# blimpy-1_0-A.net
KiCad netlist of a schematic drawn in EAGLE
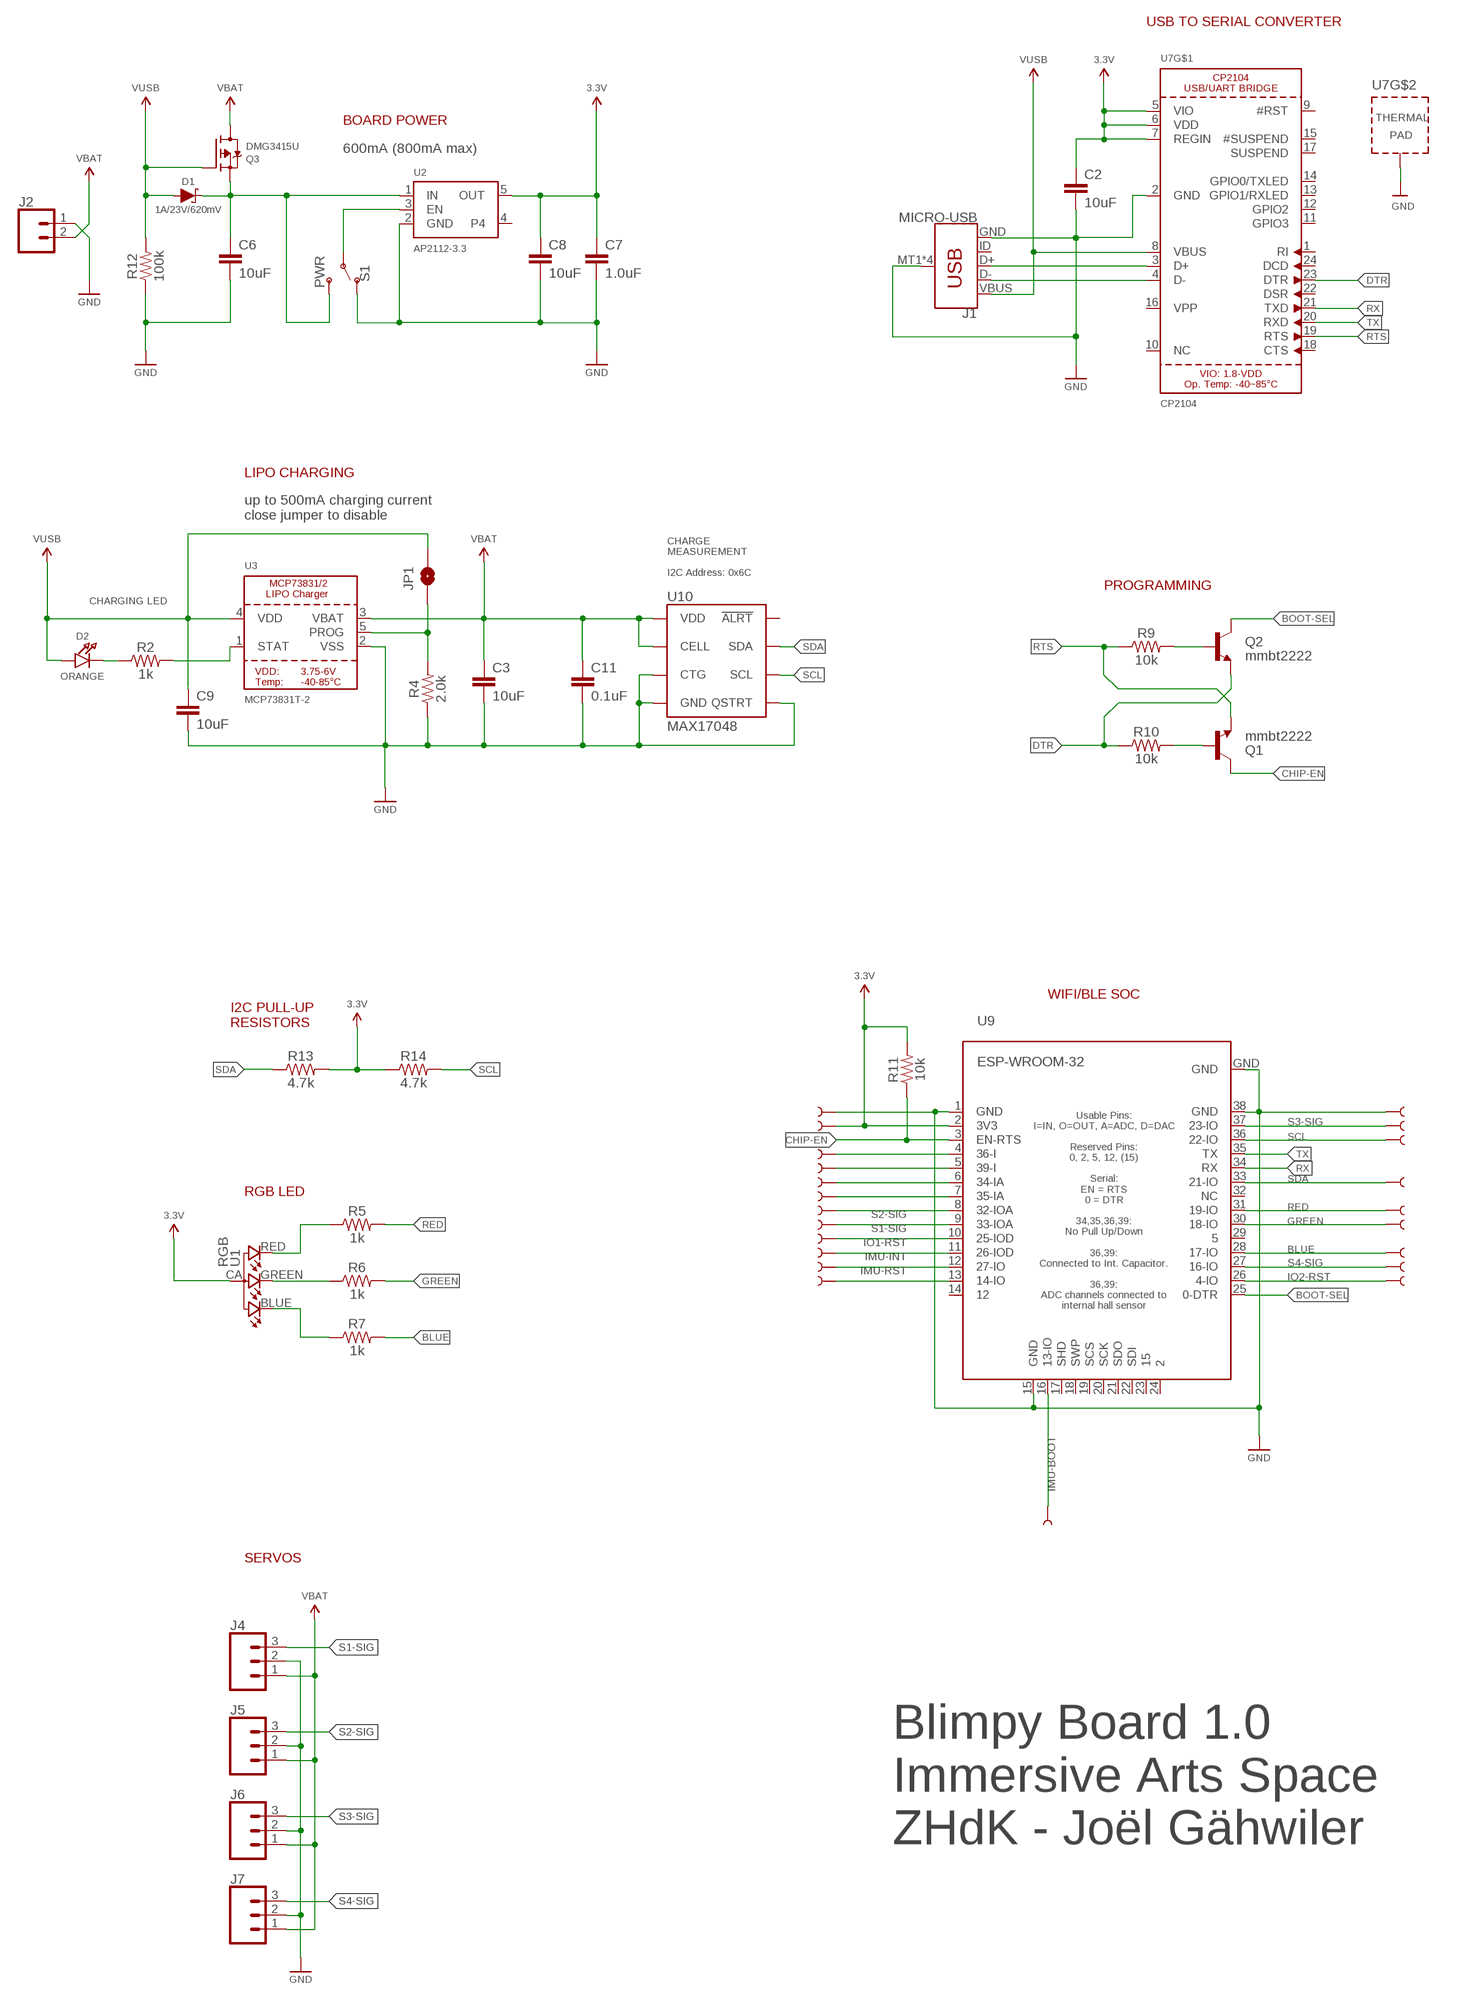
[diagram p0: schematic, sheet 1, part 1 of 2]
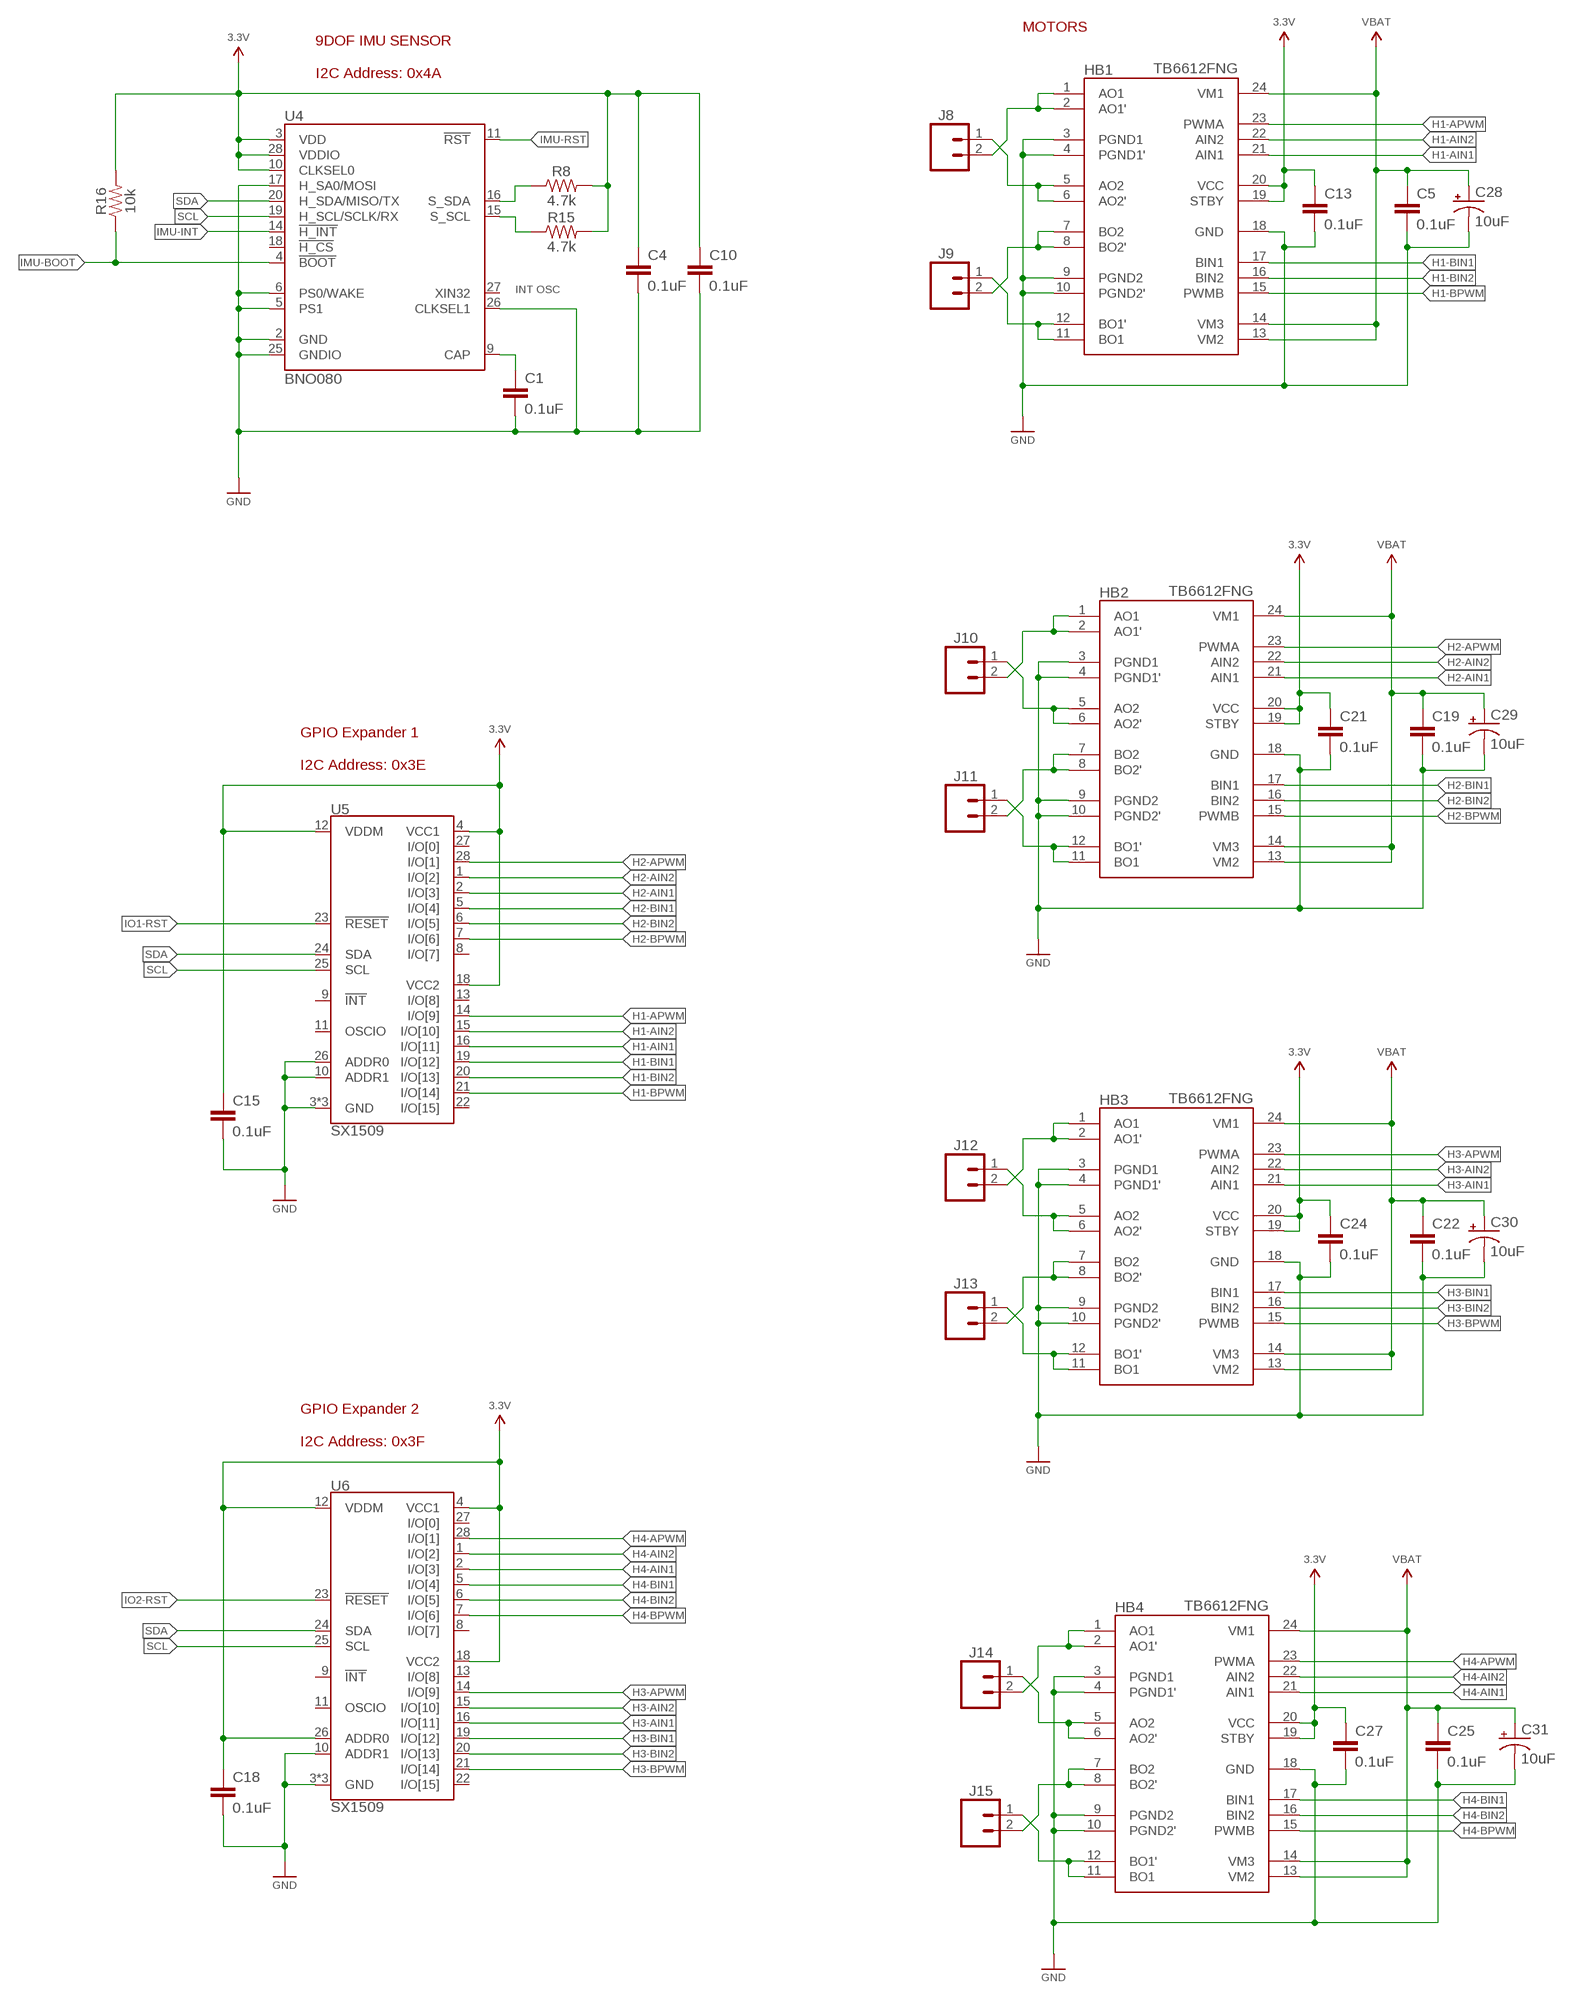
[diagram p1: schematic, sheet 1, part 2 of 2]

(export (version "E")
  (design (tool "Eeschema 10.0.6"))
  (components
    (comp (ref "C1")
      (value "0.1uF")
      (footprint "eagle-import:0603")
      (libsource (lib "eagle-import") (part "0.1UF-0603-25V-5%"))
    )
    (comp (ref "C2")
      (value "10uF")
      (footprint "eagle-import:0603")
      (libsource (lib "eagle-import") (part "10UF-0603-6.3V-20%"))
    )
    (comp (ref "C3")
      (value "10uF")
      (footprint "eagle-import:0603")
      (libsource (lib "eagle-import") (part "10UF-0603-6.3V-20%"))
    )
    (comp (ref "C4")
      (value "0.1uF")
      (footprint "eagle-import:0603")
      (libsource (lib "eagle-import") (part "0.1UF-0603-25V-5%"))
    )
    (comp (ref "C5")
      (value "0.1uF")
      (footprint "eagle-import:0603")
      (libsource (lib "eagle-import") (part "0.1UF-0603-25V-5%"))
    )
    (comp (ref "C6")
      (value "10uF")
      (footprint "eagle-import:0603")
      (libsource (lib "eagle-import") (part "10UF-0603-6.3V-20%"))
    )
    (comp (ref "C7")
      (value "1.0uF")
      (footprint "eagle-import:0603")
      (libsource (lib "eagle-import") (part "1.0UF-0603-16V-10%"))
    )
    (comp (ref "C8")
      (value "10uF")
      (footprint "eagle-import:0603")
      (libsource (lib "eagle-import") (part "10UF-0603-6.3V-20%"))
    )
    (comp (ref "C9")
      (value "10uF")
      (footprint "eagle-import:0603")
      (libsource (lib "eagle-import") (part "10UF-0603-6.3V-20%"))
    )
    (comp (ref "C10")
      (value "0.1uF")
      (footprint "eagle-import:0603")
      (libsource (lib "eagle-import") (part "0.1UF-0603-25V-5%"))
    )
    (comp (ref "C11")
      (value "0.1uF")
      (footprint "eagle-import:0603")
      (libsource (lib "eagle-import") (part "SparkFun-Capacitors_510_0.1UF-0603-25V-5%"))
    )
    (comp (ref "C13")
      (value "0.1uF")
      (footprint "eagle-import:0603")
      (libsource (lib "eagle-import") (part "0.1UF-0603-25V-5%"))
    )
    (comp (ref "C15")
      (value "0.1uF")
      (footprint "eagle-import:0603")
      (libsource (lib "eagle-import") (part "SparkFun-Capacitors_510_0.1UF-0603-25V-5%"))
    )
    (comp (ref "C18")
      (value "0.1uF")
      (footprint "eagle-import:0603")
      (libsource (lib "eagle-import") (part "SparkFun-Capacitors_510_0.1UF-0603-25V-5%"))
    )
    (comp (ref "C19")
      (value "0.1uF")
      (footprint "eagle-import:0603")
      (libsource (lib "eagle-import") (part "0.1UF-0603-25V-5%"))
    )
    (comp (ref "C21")
      (value "0.1uF")
      (footprint "eagle-import:0603")
      (libsource (lib "eagle-import") (part "0.1UF-0603-25V-5%"))
    )
    (comp (ref "C22")
      (value "0.1uF")
      (footprint "eagle-import:0603")
      (libsource (lib "eagle-import") (part "0.1UF-0603-25V-5%"))
    )
    (comp (ref "C24")
      (value "0.1uF")
      (footprint "eagle-import:0603")
      (libsource (lib "eagle-import") (part "0.1UF-0603-25V-5%"))
    )
    (comp (ref "C25")
      (value "0.1uF")
      (footprint "eagle-import:0603")
      (libsource (lib "eagle-import") (part "0.1UF-0603-25V-5%"))
    )
    (comp (ref "C27")
      (value "0.1uF")
      (footprint "eagle-import:0603")
      (libsource (lib "eagle-import") (part "0.1UF-0603-25V-5%"))
    )
    (comp (ref "C28")
      (value "10uF")
      (footprint "eagle-import:EIA3216")
      (libsource (lib "eagle-import") (part "10UF-POLAR-EIA3216-16V-10%(TANT)"))
    )
    (comp (ref "C29")
      (value "10uF")
      (footprint "eagle-import:EIA3216")
      (libsource (lib "eagle-import") (part "10UF-POLAR-EIA3216-16V-10%(TANT)"))
    )
    (comp (ref "C30")
      (value "10uF")
      (footprint "eagle-import:EIA3216")
      (libsource (lib "eagle-import") (part "10UF-POLAR-EIA3216-16V-10%(TANT)"))
    )
    (comp (ref "C31")
      (value "10uF")
      (footprint "eagle-import:EIA3216")
      (libsource (lib "eagle-import") (part "10UF-POLAR-EIA3216-16V-10%(TANT)"))
    )
    (comp (ref "D1")
      (value "1A/23V/620mV")
      (footprint "eagle-import:SOD-323")
      (libsource (lib "eagle-import") (part "DIODE-SCHOTTKY-BAT20J"))
    )
    (comp (ref "D2")
      (value "ORANGE")
      (footprint "eagle-import:CHIPLED_0805_NOOUTLINE")
      (libsource (lib "eagle-import") (part "LED0805_NOOUTLINE"))
    )
    (comp (ref "HB1")
      (value "TB6612FNG")
      (footprint "eagle-import:SSOP24")
      (libsource (lib "eagle-import") (part "TB6612FNG"))
    )
    (comp (ref "HB2")
      (value "TB6612FNG")
      (footprint "eagle-import:SSOP24")
      (libsource (lib "eagle-import") (part "TB6612FNG"))
    )
    (comp (ref "HB3")
      (value "TB6612FNG")
      (footprint "eagle-import:SSOP24")
      (libsource (lib "eagle-import") (part "TB6612FNG"))
    )
    (comp (ref "HB4")
      (value "TB6612FNG")
      (footprint "eagle-import:SSOP24")
      (libsource (lib "eagle-import") (part "TB6612FNG"))
    )
    (comp (ref "J1")
      (value "MICRO-USB")
      (footprint "eagle-import:USB-MICROB")
      (libsource (lib "eagle-import") (part "USB_MICRO-B_SMT"))
    )
    (comp (ref "J2")
      (value "CONN_02-JST-2MM-SMT")
      (footprint "eagle-import:JST-2-SMD")
      (libsource (lib "eagle-import") (part "CONN_02-JST-2MM-SMT"))
    )
    (comp (ref "J4")
      (value "3-PIN SMD")
      (footprint "eagle-import:JST-3-SMD")
      (libsource (lib "eagle-import") (part "CONN_03JST-SMD"))
    )
    (comp (ref "J5")
      (value "3-PIN SMD")
      (footprint "eagle-import:JST-3-SMD")
      (libsource (lib "eagle-import") (part "CONN_03JST-SMD"))
    )
    (comp (ref "J6")
      (value "3-PIN SMD")
      (footprint "eagle-import:JST-3-SMD")
      (libsource (lib "eagle-import") (part "CONN_03JST-SMD"))
    )
    (comp (ref "J7")
      (value "3-PIN SMD")
      (footprint "eagle-import:JST-3-SMD")
      (libsource (lib "eagle-import") (part "CONN_03JST-SMD"))
    )
    (comp (ref "J8")
      (value "CONN_02-JST-2MM-SMT")
      (footprint "eagle-import:JST-2-SMD")
      (libsource (lib "eagle-import") (part "CONN_02-JST-2MM-SMT"))
    )
    (comp (ref "J9")
      (value "CONN_02-JST-2MM-SMT")
      (footprint "eagle-import:JST-2-SMD")
      (libsource (lib "eagle-import") (part "CONN_02-JST-2MM-SMT"))
    )
    (comp (ref "J10")
      (value "CONN_02-JST-2MM-SMT")
      (footprint "eagle-import:JST-2-SMD")
      (libsource (lib "eagle-import") (part "CONN_02-JST-2MM-SMT"))
    )
    (comp (ref "J11")
      (value "CONN_02-JST-2MM-SMT")
      (footprint "eagle-import:JST-2-SMD")
      (libsource (lib "eagle-import") (part "CONN_02-JST-2MM-SMT"))
    )
    (comp (ref "J12")
      (value "CONN_02-JST-2MM-SMT")
      (footprint "eagle-import:JST-2-SMD")
      (libsource (lib "eagle-import") (part "CONN_02-JST-2MM-SMT"))
    )
    (comp (ref "J13")
      (value "CONN_02-JST-2MM-SMT")
      (footprint "eagle-import:JST-2-SMD")
      (libsource (lib "eagle-import") (part "CONN_02-JST-2MM-SMT"))
    )
    (comp (ref "J14")
      (value "CONN_02-JST-2MM-SMT")
      (footprint "eagle-import:JST-2-SMD")
      (libsource (lib "eagle-import") (part "CONN_02-JST-2MM-SMT"))
    )
    (comp (ref "J15")
      (value "CONN_02-JST-2MM-SMT")
      (footprint "eagle-import:JST-2-SMD")
      (libsource (lib "eagle-import") (part "CONN_02-JST-2MM-SMT"))
    )
    (comp (ref "JP1")
      (value "JUMPER-SMT_2_NO_SILK")
      (footprint "eagle-import:SMT-JUMPER_2_NO_SILK")
      (libsource (lib "eagle-import") (part "JUMPER-SMT_2_NO_SILK"))
    )
    (comp (ref "Q1")
      (value "mmbt2222")
      (footprint "eagle-import:SOT23-3")
      (libsource (lib "eagle-import") (part "TRANSISTOR_NPNSOT23-3"))
    )
    (comp (ref "Q2")
      (value "mmbt2222")
      (footprint "eagle-import:SOT23-3")
      (libsource (lib "eagle-import") (part "TRANSISTOR_NPNSOT23-3"))
    )
    (comp (ref "Q3")
      (value "DMG3415U")
      (footprint "eagle-import:SOT23-R")
      (libsource (lib "eagle-import") (part "MOSFET-P"))
    )
    (comp (ref "R2")
      (value "1k")
      (footprint "eagle-import:0603")
      (libsource (lib "eagle-import") (part "1KOHM-0603-1/10W-1%"))
    )
    (comp (ref "R4")
      (value "2.0k")
      (footprint "eagle-import:0603")
      (libsource (lib "eagle-import") (part "2.0KOHM-0603-1/10W-5%"))
    )
    (comp (ref "R5")
      (value "1k")
      (footprint "eagle-import:0603")
      (libsource (lib "eagle-import") (part "1KOHM-0603-1/10W-1%"))
    )
    (comp (ref "R6")
      (value "1k")
      (footprint "eagle-import:0603")
      (libsource (lib "eagle-import") (part "1KOHM-0603-1/10W-1%"))
    )
    (comp (ref "R7")
      (value "1k")
      (footprint "eagle-import:0603")
      (libsource (lib "eagle-import") (part "1KOHM-0603-1/10W-1%"))
    )
    (comp (ref "R8")
      (value "4.7k")
      (footprint "eagle-import:0603")
      (libsource (lib "eagle-import") (part "4.7KOHM-0603-1/10W-1%"))
    )
    (comp (ref "R9")
      (value "10k")
      (footprint "eagle-import:0603")
      (libsource (lib "eagle-import") (part "10KOHM-0603-1/10W-1%"))
    )
    (comp (ref "R10")
      (value "10k")
      (footprint "eagle-import:0603")
      (libsource (lib "eagle-import") (part "10KOHM-0603-1/10W-1%"))
    )
    (comp (ref "R11")
      (value "10k")
      (footprint "eagle-import:0603")
      (libsource (lib "eagle-import") (part "10KOHM-0603-1/10W-1%"))
    )
    (comp (ref "R12")
      (value "100k")
      (footprint "eagle-import:0603")
      (libsource (lib "eagle-import") (part "100KOHM-0603-1/10W-1%"))
    )
    (comp (ref "R13")
      (value "4.7k")
      (footprint "eagle-import:0603")
      (libsource (lib "eagle-import") (part "4.7KOHM-0603-1/10W-1%"))
    )
    (comp (ref "R14")
      (value "4.7k")
      (footprint "eagle-import:0603")
      (libsource (lib "eagle-import") (part "4.7KOHM-0603-1/10W-1%"))
    )
    (comp (ref "R15")
      (value "4.7k")
      (footprint "eagle-import:0603")
      (libsource (lib "eagle-import") (part "4.7KOHM-0603-1/10W-1%"))
    )
    (comp (ref "R16")
      (value "10k")
      (footprint "eagle-import:0603")
      (libsource (lib "eagle-import") (part "10KOHM-0603-1/10W-1%"))
    )
    (comp (ref "S1")
      (value "PWR")
      (footprint "eagle-import:SWITCH_SPST_SMD_A")
      (libsource (lib "eagle-import") (part "SWITCH-SPDT-SMD-RIGHT-ANGLE"))
    )
    (comp (ref "TP1")
      (value "TEST-POINT3")
      (footprint "eagle-import:PAD.03X.03")
      (libsource (lib "eagle-import") (part "TEST-POINT3"))
    )
    (comp (ref "TP2")
      (value "TEST-POINT3")
      (footprint "eagle-import:PAD.03X.03")
      (libsource (lib "eagle-import") (part "TEST-POINT3"))
    )
    (comp (ref "TP3")
      (value "TEST-POINT3")
      (footprint "eagle-import:PAD.03X.03")
      (libsource (lib "eagle-import") (part "TEST-POINT3"))
    )
    (comp (ref "TP4")
      (value "TEST-POINT3")
      (footprint "eagle-import:PAD.03X.03")
      (libsource (lib "eagle-import") (part "TEST-POINT3"))
    )
    (comp (ref "TP5")
      (value "TEST-POINT3")
      (footprint "eagle-import:PAD.03X.03")
      (libsource (lib "eagle-import") (part "TEST-POINT3"))
    )
    (comp (ref "TP6")
      (value "TEST-POINT3")
      (footprint "eagle-import:PAD.03X.03")
      (libsource (lib "eagle-import") (part "TEST-POINT3"))
    )
    (comp (ref "TP7")
      (value "TEST-POINT3")
      (footprint "eagle-import:PAD.03X.03")
      (libsource (lib "eagle-import") (part "TEST-POINT3"))
    )
    (comp (ref "TP8")
      (value "TEST-POINT3")
      (footprint "eagle-import:PAD.03X.03")
      (libsource (lib "eagle-import") (part "TEST-POINT3"))
    )
    (comp (ref "TP9")
      (value "TEST-POINT3")
      (footprint "eagle-import:PAD.03X.03")
      (libsource (lib "eagle-import") (part "TEST-POINT3"))
    )
    (comp (ref "TP10")
      (value "TEST-POINT3")
      (footprint "eagle-import:PAD.03X.03")
      (libsource (lib "eagle-import") (part "TEST-POINT3"))
    )
    (comp (ref "TP11")
      (value "TEST-POINT3")
      (footprint "eagle-import:PAD.03X.03")
      (libsource (lib "eagle-import") (part "TEST-POINT3"))
    )
    (comp (ref "TP12")
      (value "TEST-POINT3")
      (footprint "eagle-import:PAD.03X.03")
      (libsource (lib "eagle-import") (part "TEST-POINT3"))
    )
    (comp (ref "TP13")
      (value "TEST-POINT3")
      (footprint "eagle-import:PAD.03X.03")
      (libsource (lib "eagle-import") (part "TEST-POINT3"))
    )
    (comp (ref "TP14")
      (value "TEST-POINT3")
      (footprint "eagle-import:PAD.03X.03")
      (libsource (lib "eagle-import") (part "TEST-POINT3"))
    )
    (comp (ref "TP15")
      (value "TEST-POINT3")
      (footprint "eagle-import:PAD.03X.03")
      (libsource (lib "eagle-import") (part "TEST-POINT3"))
    )
    (comp (ref "TP16")
      (value "TEST-POINT3")
      (footprint "eagle-import:PAD.03X.03")
      (libsource (lib "eagle-import") (part "TEST-POINT3"))
    )
    (comp (ref "TP17")
      (value "TEST-POINT3")
      (footprint "eagle-import:PAD.03X.03")
      (libsource (lib "eagle-import") (part "TEST-POINT3"))
    )
    (comp (ref "TP18")
      (value "TEST-POINT3")
      (footprint "eagle-import:PAD.03X.03")
      (libsource (lib "eagle-import") (part "TEST-POINT3"))
    )
    (comp (ref "TP19")
      (value "TEST-POINT3")
      (footprint "eagle-import:PAD.03X.03")
      (libsource (lib "eagle-import") (part "TEST-POINT3"))
    )
    (comp (ref "TP20")
      (value "TEST-POINT3")
      (footprint "eagle-import:PAD.03X.03")
      (libsource (lib "eagle-import") (part "TEST-POINT3"))
    )
    (comp (ref "TP21")
      (value "TEST-POINT3")
      (footprint "eagle-import:PAD.03X.03")
      (libsource (lib "eagle-import") (part "TEST-POINT3"))
    )
    (comp (ref "TP22")
      (value "TEST-POINT3")
      (footprint "eagle-import:PAD.03X.03")
      (libsource (lib "eagle-import") (part "TEST-POINT3"))
    )
    (comp (ref "U1")
      (value "RGB")
      (footprint "eagle-import:PLCC4-2MM-RGB")
      (libsource (lib "eagle-import") (part "RGB-LED-CLMVB-FKARGB"))
    )
    (comp (ref "U2")
      (value "AP2112-3.3")
      (footprint "eagle-import:SOT23-5")
      (libsource (lib "eagle-import") (part "VREG_SOT23-5"))
    )
    (comp (ref "U3")
      (value "MCP73831T-2")
      (footprint "eagle-import:SOT23-5")
      (libsource (lib "eagle-import") (part "MCP73831/2"))
    )
    (comp (ref "U4")
      (value "BNO080")
      (footprint "eagle-import:LGA-28")
      (libsource (lib "eagle-import") (part "BNO080"))
    )
    (comp (ref "U5")
      (value "SX1509")
      (footprint "eagle-import:QFN-28")
      (libsource (lib "eagle-import") (part "SX1509"))
    )
    (comp (ref "U6")
      (value "SX1509")
      (footprint "eagle-import:QFN-28")
      (libsource (lib "eagle-import") (part "SX1509"))
    )
    (comp (ref "U7")
      (value "CP2104")
      (footprint "eagle-import:QFN24_4MM_SMSC")
      (libsource (lib "eagle-import") (part "CP2104"))
    )
    (comp (ref "U9")
      (value "ESP-WROOM-32")
      (footprint "eagle-import:ESP-WROOM-32")
      (libsource (lib "eagle-import") (part "ESP-WROOM-32"))
    )
    (comp (ref "U10")
      (value "MAX17048")
      (footprint "eagle-import:DFN-8")
      (libsource (lib "eagle-import") (part "MAX17048DFN8"))
    )
  )
  (nets
    (net (code "1") (name "3.3V") (class "Default")
      (node (ref "C10") (pin "1") (pinfunction "1_1") (pintype "passive"))
      (node (ref "C13") (pin "1") (pinfunction "1_1") (pintype "passive"))
      (node (ref "C15") (pin "1") (pinfunction "1_1") (pintype "passive"))
      (node (ref "C18") (pin "1") (pinfunction "1_1") (pintype "passive"))
      (node (ref "C2") (pin "1") (pinfunction "1_1") (pintype "passive"))
      (node (ref "C21") (pin "1") (pinfunction "1_1") (pintype "passive"))
      (node (ref "C24") (pin "1") (pinfunction "1_1") (pintype "passive"))
      (node (ref "C27") (pin "1") (pinfunction "1_1") (pintype "passive"))
      (node (ref "C4") (pin "1") (pinfunction "1_1") (pintype "passive"))
      (node (ref "C7") (pin "1") (pinfunction "1_1") (pintype "passive"))
      (node (ref "C8") (pin "1") (pinfunction "1_1") (pintype "passive"))
      (node (ref "HB1") (pin "19") (pinfunction "STBY_19") (pintype "input"))
      (node (ref "HB1") (pin "20") (pinfunction "VCC_20") (pintype "power_in"))
      (node (ref "HB2") (pin "19") (pinfunction "STBY_19") (pintype "input"))
      (node (ref "HB2") (pin "20") (pinfunction "VCC_20") (pintype "power_in"))
      (node (ref "HB3") (pin "19") (pinfunction "STBY_19") (pintype "input"))
      (node (ref "HB3") (pin "20") (pinfunction "VCC_20") (pintype "power_in"))
      (node (ref "HB4") (pin "19") (pinfunction "STBY_19") (pintype "input"))
      (node (ref "HB4") (pin "20") (pinfunction "VCC_20") (pintype "power_in"))
      (node (ref "R11") (pin "2") (pinfunction "2_2") (pintype "passive"))
      (node (ref "R13") (pin "2") (pinfunction "2_2") (pintype "passive"))
      (node (ref "R14") (pin "1") (pinfunction "1_1") (pintype "passive"))
      (node (ref "R15") (pin "2") (pinfunction "2_2") (pintype "passive"))
      (node (ref "R16") (pin "2") (pinfunction "2_2") (pintype "passive"))
      (node (ref "R8") (pin "2") (pinfunction "2_2") (pintype "passive"))
      (node (ref "TP11") (pin "P$1") (pinfunction "1_P$1") (pintype "bidirectional"))
      (node (ref "U1") (pin "CA") (pinfunction "1_CA") (pintype "passive"))
      (node (ref "U2") (pin "5") (pinfunction "OUT_5") (pintype "power_in"))
      (node (ref "U4") (pin "10") (pinfunction "CLKSEL0_10") (pintype "bidirectional"))
      (node (ref "U4") (pin "28") (pinfunction "VDDIO_28") (pintype "bidirectional"))
      (node (ref "U4") (pin "3") (pinfunction "VDD_3") (pintype "bidirectional"))
      (node (ref "U5") (pin "12") (pinfunction "VDDM_12") (pintype "bidirectional"))
      (node (ref "U5") (pin "18") (pinfunction "VCC2_18") (pintype "bidirectional"))
      (node (ref "U5") (pin "4") (pinfunction "VCC1_4") (pintype "bidirectional"))
      (node (ref "U6") (pin "12") (pinfunction "VDDM_12") (pintype "bidirectional"))
      (node (ref "U6") (pin "18") (pinfunction "VCC2_18") (pintype "bidirectional"))
      (node (ref "U6") (pin "26") (pinfunction "ADDR0_26") (pintype "bidirectional"))
      (node (ref "U6") (pin "4") (pinfunction "VCC1_4") (pintype "bidirectional"))
      (node (ref "U7") (pin "5") (pinfunction "VIO_5") (pintype "power_in"))
      (node (ref "U7") (pin "6") (pinfunction "VDD_6") (pintype "power_in"))
      (node (ref "U7") (pin "7") (pinfunction "REGIN_7") (pintype "power_in"))
      (node (ref "U9") (pin "2") (pinfunction "3V3_2") (pintype "bidirectional"))
    )
    (net (code "2") (name "BLUE") (class "Default")
      (node (ref "R7") (pin "2") (pinfunction "2_2") (pintype "passive"))
      (node (ref "TP22") (pin "P$1") (pinfunction "1_P$1") (pintype "bidirectional"))
      (node (ref "U9") (pin "28") (pinfunction "17-IO_28") (pintype "bidirectional"))
    )
    (net (code "3") (name "BOOT-SEL") (class "Default")
      (node (ref "Q2") (pin "3") (pinfunction "C_3") (pintype "passive"))
      (node (ref "U9") (pin "25") (pinfunction "0-DTR_25") (pintype "bidirectional"))
    )
    (net (code "4") (name "CHIP-EN") (class "Default")
      (node (ref "Q1") (pin "3") (pinfunction "C_3") (pintype "passive"))
      (node (ref "R11") (pin "1") (pinfunction "1_1") (pintype "passive"))
      (node (ref "U9") (pin "3") (pinfunction "EN-RTS_3") (pintype "bidirectional"))
    )
    (net (code "5") (name "DTR") (class "Default")
      (node (ref "Q2") (pin "2") (pinfunction "E_2") (pintype "passive"))
      (node (ref "R10") (pin "1") (pinfunction "1_1") (pintype "passive"))
      (node (ref "U7") (pin "23") (pinfunction "DTR_23") (pintype "output"))
    )
    (net (code "6") (name "GND") (class "Default")
      (node (ref "C1") (pin "2") (pinfunction "2_2") (pintype "passive"))
      (node (ref "C10") (pin "2") (pinfunction "2_2") (pintype "passive"))
      (node (ref "C11") (pin "2") (pinfunction "2_2") (pintype "passive"))
      (node (ref "C13") (pin "2") (pinfunction "2_2") (pintype "passive"))
      (node (ref "C15") (pin "2") (pinfunction "2_2") (pintype "passive"))
      (node (ref "C18") (pin "2") (pinfunction "2_2") (pintype "passive"))
      (node (ref "C19") (pin "2") (pinfunction "2_2") (pintype "passive"))
      (node (ref "C2") (pin "2") (pinfunction "2_2") (pintype "passive"))
      (node (ref "C21") (pin "2") (pinfunction "2_2") (pintype "passive"))
      (node (ref "C22") (pin "2") (pinfunction "2_2") (pintype "passive"))
      (node (ref "C24") (pin "2") (pinfunction "2_2") (pintype "passive"))
      (node (ref "C25") (pin "2") (pinfunction "2_2") (pintype "passive"))
      (node (ref "C27") (pin "2") (pinfunction "2_2") (pintype "passive"))
      (node (ref "C28") (pin "-") (pinfunction "-_-") (pintype "passive"))
      (node (ref "C29") (pin "-") (pinfunction "-_-") (pintype "passive"))
      (node (ref "C3") (pin "2") (pinfunction "2_2") (pintype "passive"))
      (node (ref "C30") (pin "-") (pinfunction "-_-") (pintype "passive"))
      (node (ref "C31") (pin "-") (pinfunction "-_-") (pintype "passive"))
      (node (ref "C4") (pin "2") (pinfunction "2_2") (pintype "passive"))
      (node (ref "C5") (pin "2") (pinfunction "2_2") (pintype "passive"))
      (node (ref "C6") (pin "2") (pinfunction "2_2") (pintype "passive"))
      (node (ref "C7") (pin "2") (pinfunction "2_2") (pintype "passive"))
      (node (ref "C8") (pin "2") (pinfunction "2_2") (pintype "passive"))
      (node (ref "C9") (pin "2") (pinfunction "2_2") (pintype "passive"))
      (node (ref "HB1") (pin "10") (pinfunction "PGND2'_10") (pintype "power_in"))
      (node (ref "HB1") (pin "18") (pinfunction "GND_18") (pintype "power_in"))
      (node (ref "HB1") (pin "3") (pinfunction "PGND1_3") (pintype "power_in"))
      (node (ref "HB1") (pin "4") (pinfunction "PGND1'_4") (pintype "power_in"))
      (node (ref "HB1") (pin "9") (pinfunction "PGND2_9") (pintype "power_in"))
      (node (ref "HB2") (pin "10") (pinfunction "PGND2'_10") (pintype "power_in"))
      (node (ref "HB2") (pin "18") (pinfunction "GND_18") (pintype "power_in"))
      (node (ref "HB2") (pin "3") (pinfunction "PGND1_3") (pintype "power_in"))
      (node (ref "HB2") (pin "4") (pinfunction "PGND1'_4") (pintype "power_in"))
      (node (ref "HB2") (pin "9") (pinfunction "PGND2_9") (pintype "power_in"))
      (node (ref "HB3") (pin "10") (pinfunction "PGND2'_10") (pintype "power_in"))
      (node (ref "HB3") (pin "18") (pinfunction "GND_18") (pintype "power_in"))
      (node (ref "HB3") (pin "3") (pinfunction "PGND1_3") (pintype "power_in"))
      (node (ref "HB3") (pin "4") (pinfunction "PGND1'_4") (pintype "power_in"))
      (node (ref "HB3") (pin "9") (pinfunction "PGND2_9") (pintype "power_in"))
      (node (ref "HB4") (pin "10") (pinfunction "PGND2'_10") (pintype "power_in"))
      (node (ref "HB4") (pin "18") (pinfunction "GND_18") (pintype "power_in"))
      (node (ref "HB4") (pin "3") (pinfunction "PGND1_3") (pintype "power_in"))
      (node (ref "HB4") (pin "4") (pinfunction "PGND1'_4") (pintype "power_in"))
      (node (ref "HB4") (pin "9") (pinfunction "PGND2_9") (pintype "power_in"))
      (node (ref "J1") (pin "GND") (pinfunction "GND_GND") (pintype "power_in"))
      (node (ref "J1") (pin "MT1") (pinfunction "SHIELD_MT1") (pintype "bidirectional"))
      (node (ref "J1") (pin "MT2") (pinfunction "SHIELD_MT2") (pintype "bidirectional"))
      (node (ref "J1") (pin "P$1") (pinfunction "SHIELD_P$1") (pintype "bidirectional"))
      (node (ref "J1") (pin "P$2") (pinfunction "SHIELD_P$2") (pintype "bidirectional"))
      (node (ref "J2") (pin "1") (pinfunction "2_1") (pintype "passive"))
      (node (ref "J4") (pin "2") (pinfunction "2_2") (pintype "passive"))
      (node (ref "J5") (pin "2") (pinfunction "2_2") (pintype "passive"))
      (node (ref "J6") (pin "2") (pinfunction "2_2") (pintype "passive"))
      (node (ref "J7") (pin "2") (pinfunction "2_2") (pintype "passive"))
      (node (ref "R12") (pin "1") (pinfunction "1_1") (pintype "passive"))
      (node (ref "R4") (pin "1") (pinfunction "1_1") (pintype "passive"))
      (node (ref "S1") (pin "1") (pinfunction "O_1") (pintype "passive"))
      (node (ref "TP12") (pin "P$1") (pinfunction "1_P$1") (pintype "bidirectional"))
      (node (ref "TP13") (pin "P$1") (pinfunction "1_P$1") (pintype "bidirectional"))
      (node (ref "U10") (pin "P$1") (pinfunction "CTG_P$1") (pintype "input"))
      (node (ref "U10") (pin "P$4") (pinfunction "GND_P$4") (pintype "bidirectional"))
      (node (ref "U10") (pin "P$6") (pinfunction "QSTRT_P$6") (pintype "bidirectional"))
      (node (ref "U10") (pin "P$9") (pinfunction "GND_P$9") (pintype "bidirectional"))
      (node (ref "U2") (pin "2") (pinfunction "GND_2") (pintype "power_in"))
      (node (ref "U3") (pin "2") (pinfunction "VSS_2") (pintype "power_in"))
      (node (ref "U4") (pin "17") (pinfunction "H_SA0/MOSI_17") (pintype "bidirectional"))
      (node (ref "U4") (pin "2") (pinfunction "GND_2") (pintype "bidirectional"))
      (node (ref "U4") (pin "25") (pinfunction "GNDIO_25") (pintype "bidirectional"))
      (node (ref "U4") (pin "26") (pinfunction "CLKSEL1_26") (pintype "bidirectional"))
      (node (ref "U4") (pin "5") (pinfunction "PS1_5") (pintype "bidirectional"))
      (node (ref "U4") (pin "6") (pinfunction "PS0/WAKE_6") (pintype "bidirectional"))
      (node (ref "U5") (pin "10") (pinfunction "ADDR1_10") (pintype "bidirectional"))
      (node (ref "U5") (pin "17") (pinfunction "GND_17") (pintype "bidirectional"))
      (node (ref "U5") (pin "26") (pinfunction "ADDR0_26") (pintype "bidirectional"))
      (node (ref "U5") (pin "29") (pinfunction "GND_29") (pintype "bidirectional"))
      (node (ref "U5") (pin "3") (pinfunction "GND_3") (pintype "bidirectional"))
      (node (ref "U6") (pin "10") (pinfunction "ADDR1_10") (pintype "bidirectional"))
      (node (ref "U6") (pin "17") (pinfunction "GND_17") (pintype "bidirectional"))
      (node (ref "U6") (pin "29") (pinfunction "GND_29") (pintype "bidirectional"))
      (node (ref "U6") (pin "3") (pinfunction "GND_3") (pintype "bidirectional"))
      (node (ref "U7") (pin "2") (pinfunction "GND_2") (pintype "power_in"))
      (node (ref "U7") (pin "THERM") (pinfunction "TP_THERM") (pintype "power_in"))
      (node (ref "U9") (pin "1") (pinfunction "GND_1") (pintype "bidirectional"))
      (node (ref "U9") (pin "15") (pinfunction "GND_15") (pintype "bidirectional"))
      (node (ref "U9") (pin "38") (pinfunction "GND_38") (pintype "bidirectional"))
      (node (ref "U9") (pin "GND") (pinfunction "GND_GND") (pintype "bidirectional"))
    )
    (net (code "7") (name "GREEN") (class "Default")
      (node (ref "R6") (pin "2") (pinfunction "2_2") (pintype "passive"))
      (node (ref "TP21") (pin "P$1") (pinfunction "1_P$1") (pintype "bidirectional"))
      (node (ref "U9") (pin "30") (pinfunction "18-IO_30") (pintype "bidirectional"))
    )
    (net (code "8") (name "H1-AIN1") (class "Default")
      (node (ref "HB1") (pin "21") (pinfunction "AIN1_21") (pintype "input"))
      (node (ref "U5") (pin "16") (pinfunction "I/O[11]_16") (pintype "bidirectional"))
    )
    (net (code "9") (name "H1-AIN2") (class "Default")
      (node (ref "HB1") (pin "22") (pinfunction "AIN2_22") (pintype "input"))
      (node (ref "U5") (pin "15") (pinfunction "I/O[10]_15") (pintype "bidirectional"))
    )
    (net (code "10") (name "H1-APWM") (class "Default")
      (node (ref "HB1") (pin "23") (pinfunction "PWMA_23") (pintype "input"))
      (node (ref "U5") (pin "14") (pinfunction "I/O[9]_14") (pintype "bidirectional"))
    )
    (net (code "11") (name "H1-BIN1") (class "Default")
      (node (ref "HB1") (pin "17") (pinfunction "BIN1_17") (pintype "input"))
      (node (ref "U5") (pin "19") (pinfunction "I/O[12]_19") (pintype "bidirectional"))
    )
    (net (code "12") (name "H1-BIN2") (class "Default")
      (node (ref "HB1") (pin "16") (pinfunction "BIN2_16") (pintype "input"))
      (node (ref "U5") (pin "20") (pinfunction "I/O[13]_20") (pintype "bidirectional"))
    )
    (net (code "13") (name "H1-BPWM") (class "Default")
      (node (ref "HB1") (pin "15") (pinfunction "PWMB_15") (pintype "input"))
      (node (ref "U5") (pin "21") (pinfunction "I/O[14]_21") (pintype "bidirectional"))
    )
    (net (code "14") (name "H2-AIN1") (class "Default")
      (node (ref "HB2") (pin "21") (pinfunction "AIN1_21") (pintype "input"))
      (node (ref "U5") (pin "2") (pinfunction "I/O[3]_2") (pintype "bidirectional"))
    )
    (net (code "15") (name "H2-AIN2") (class "Default")
      (node (ref "HB2") (pin "22") (pinfunction "AIN2_22") (pintype "input"))
      (node (ref "U5") (pin "1") (pinfunction "I/O[2]_1") (pintype "bidirectional"))
    )
    (net (code "16") (name "H2-APWM") (class "Default")
      (node (ref "HB2") (pin "23") (pinfunction "PWMA_23") (pintype "input"))
      (node (ref "U5") (pin "28") (pinfunction "I/O[1]_28") (pintype "bidirectional"))
    )
    (net (code "17") (name "H2-BIN1") (class "Default")
      (node (ref "HB2") (pin "17") (pinfunction "BIN1_17") (pintype "input"))
      (node (ref "U5") (pin "5") (pinfunction "I/O[4]_5") (pintype "bidirectional"))
    )
    (net (code "18") (name "H2-BIN2") (class "Default")
      (node (ref "HB2") (pin "16") (pinfunction "BIN2_16") (pintype "input"))
      (node (ref "U5") (pin "6") (pinfunction "I/O[5]_6") (pintype "bidirectional"))
    )
    (net (code "19") (name "H2-BPWM") (class "Default")
      (node (ref "HB2") (pin "15") (pinfunction "PWMB_15") (pintype "input"))
      (node (ref "U5") (pin "7") (pinfunction "I/O[6]_7") (pintype "bidirectional"))
    )
    (net (code "20") (name "H3-AIN1") (class "Default")
      (node (ref "HB3") (pin "21") (pinfunction "AIN1_21") (pintype "input"))
      (node (ref "U6") (pin "16") (pinfunction "I/O[11]_16") (pintype "bidirectional"))
    )
    (net (code "21") (name "H3-AIN2") (class "Default")
      (node (ref "HB3") (pin "22") (pinfunction "AIN2_22") (pintype "input"))
      (node (ref "U6") (pin "15") (pinfunction "I/O[10]_15") (pintype "bidirectional"))
    )
    (net (code "22") (name "H3-APWM") (class "Default")
      (node (ref "HB3") (pin "23") (pinfunction "PWMA_23") (pintype "input"))
      (node (ref "U6") (pin "14") (pinfunction "I/O[9]_14") (pintype "bidirectional"))
    )
    (net (code "23") (name "H3-BIN1") (class "Default")
      (node (ref "HB3") (pin "17") (pinfunction "BIN1_17") (pintype "input"))
      (node (ref "U6") (pin "19") (pinfunction "I/O[12]_19") (pintype "bidirectional"))
    )
    (net (code "24") (name "H3-BIN2") (class "Default")
      (node (ref "HB3") (pin "16") (pinfunction "BIN2_16") (pintype "input"))
      (node (ref "U6") (pin "20") (pinfunction "I/O[13]_20") (pintype "bidirectional"))
    )
    (net (code "25") (name "H3-BPWM") (class "Default")
      (node (ref "HB3") (pin "15") (pinfunction "PWMB_15") (pintype "input"))
      (node (ref "U6") (pin "21") (pinfunction "I/O[14]_21") (pintype "bidirectional"))
    )
    (net (code "26") (name "H4-AIN1") (class "Default")
      (node (ref "HB4") (pin "21") (pinfunction "AIN1_21") (pintype "input"))
      (node (ref "U6") (pin "2") (pinfunction "I/O[3]_2") (pintype "bidirectional"))
    )
    (net (code "27") (name "H4-AIN2") (class "Default")
      (node (ref "HB4") (pin "22") (pinfunction "AIN2_22") (pintype "input"))
      (node (ref "U6") (pin "1") (pinfunction "I/O[2]_1") (pintype "bidirectional"))
    )
    (net (code "28") (name "H4-APWM") (class "Default")
      (node (ref "HB4") (pin "23") (pinfunction "PWMA_23") (pintype "input"))
      (node (ref "U6") (pin "28") (pinfunction "I/O[1]_28") (pintype "bidirectional"))
    )
    (net (code "29") (name "H4-BIN1") (class "Default")
      (node (ref "HB4") (pin "17") (pinfunction "BIN1_17") (pintype "input"))
      (node (ref "U6") (pin "5") (pinfunction "I/O[4]_5") (pintype "bidirectional"))
    )
    (net (code "30") (name "H4-BIN2") (class "Default")
      (node (ref "HB4") (pin "16") (pinfunction "BIN2_16") (pintype "input"))
      (node (ref "U6") (pin "6") (pinfunction "I/O[5]_6") (pintype "bidirectional"))
    )
    (net (code "31") (name "H4-BPWM") (class "Default")
      (node (ref "HB4") (pin "15") (pinfunction "PWMB_15") (pintype "input"))
      (node (ref "U6") (pin "7") (pinfunction "I/O[6]_7") (pintype "bidirectional"))
    )
    (net (code "32") (name "IMU-BOOT") (class "Default")
      (node (ref "R16") (pin "1") (pinfunction "1_1") (pintype "passive"))
      (node (ref "TP17") (pin "P$1") (pinfunction "1_P$1") (pintype "bidirectional"))
      (node (ref "U4") (pin "4") (pinfunction "~{BOOT}_4") (pintype "bidirectional"))
      (node (ref "U9") (pin "16") (pinfunction "13-IO_16") (pintype "bidirectional"))
    )
    (net (code "33") (name "IMU-INT") (class "Default")
      (node (ref "TP4") (pin "P$1") (pinfunction "1_P$1") (pintype "bidirectional"))
      (node (ref "U4") (pin "14") (pinfunction "~{H_INT}_14") (pintype "bidirectional"))
      (node (ref "U9") (pin "11") (pinfunction "26-IOD_11") (pintype "bidirectional"))
    )
    (net (code "34") (name "IMU-RST") (class "Default")
      (node (ref "TP5") (pin "P$1") (pinfunction "1_P$1") (pintype "bidirectional"))
      (node (ref "U4") (pin "11") (pinfunction "~{RST}_11") (pintype "bidirectional"))
      (node (ref "U9") (pin "12") (pinfunction "27-IO_12") (pintype "bidirectional"))
    )
    (net (code "35") (name "IO1-RST") (class "Default")
      (node (ref "TP3") (pin "P$1") (pinfunction "1_P$1") (pintype "bidirectional"))
      (node (ref "U5") (pin "23") (pinfunction "~{RESET}_23") (pintype "bidirectional"))
      (node (ref "U9") (pin "10") (pinfunction "25-IOD_10") (pintype "bidirectional"))
    )
    (net (code "36") (name "IO2-RST") (class "Default")
      (node (ref "TP16") (pin "P$1") (pinfunction "1_P$1") (pintype "bidirectional"))
      (node (ref "U6") (pin "23") (pinfunction "~{RESET}_23") (pintype "bidirectional"))
      (node (ref "U9") (pin "26") (pinfunction "4-IO_26") (pintype "bidirectional"))
    )
    (net (code "37") (name "Net-(D2-PadC)") (class "Default")
      (node (ref "D2") (pin "C") (pinfunction "C_C") (pintype "passive"))
      (node (ref "R2") (pin "1") (pinfunction "1_1") (pintype "passive"))
    )
    (net (code "38") (name "Net-(HB1-AO1')") (class "Default")
      (node (ref "HB1") (pin "1") (pinfunction "AO1_1") (pintype "output"))
      (node (ref "HB1") (pin "2") (pinfunction "AO1'_2") (pintype "output"))
      (node (ref "J8") (pin "2") (pinfunction "1_2") (pintype "passive"))
    )
    (net (code "39") (name "Net-(HB1-AO2')") (class "Default")
      (node (ref "HB1") (pin "5") (pinfunction "AO2_5") (pintype "output"))
      (node (ref "HB1") (pin "6") (pinfunction "AO2'_6") (pintype "output"))
      (node (ref "J8") (pin "1") (pinfunction "2_1") (pintype "passive"))
    )
    (net (code "40") (name "Net-(HB1-BO1')") (class "Default")
      (node (ref "HB1") (pin "11") (pinfunction "BO1_11") (pintype "output"))
      (node (ref "HB1") (pin "12") (pinfunction "BO1'_12") (pintype "output"))
      (node (ref "J9") (pin "1") (pinfunction "2_1") (pintype "passive"))
    )
    (net (code "41") (name "Net-(HB1-BO2')") (class "Default")
      (node (ref "HB1") (pin "7") (pinfunction "BO2_7") (pintype "output"))
      (node (ref "HB1") (pin "8") (pinfunction "BO2'_8") (pintype "output"))
      (node (ref "J9") (pin "2") (pinfunction "1_2") (pintype "passive"))
    )
    (net (code "42") (name "Net-(HB2-AO1')") (class "Default")
      (node (ref "HB2") (pin "1") (pinfunction "AO1_1") (pintype "output"))
      (node (ref "HB2") (pin "2") (pinfunction "AO1'_2") (pintype "output"))
      (node (ref "J10") (pin "2") (pinfunction "1_2") (pintype "passive"))
    )
    (net (code "43") (name "Net-(HB2-AO2')") (class "Default")
      (node (ref "HB2") (pin "5") (pinfunction "AO2_5") (pintype "output"))
      (node (ref "HB2") (pin "6") (pinfunction "AO2'_6") (pintype "output"))
      (node (ref "J10") (pin "1") (pinfunction "2_1") (pintype "passive"))
    )
    (net (code "44") (name "Net-(HB2-BO1')") (class "Default")
      (node (ref "HB2") (pin "11") (pinfunction "BO1_11") (pintype "output"))
      (node (ref "HB2") (pin "12") (pinfunction "BO1'_12") (pintype "output"))
      (node (ref "J11") (pin "1") (pinfunction "2_1") (pintype "passive"))
    )
    (net (code "45") (name "Net-(HB2-BO2')") (class "Default")
      (node (ref "HB2") (pin "7") (pinfunction "BO2_7") (pintype "output"))
      (node (ref "HB2") (pin "8") (pinfunction "BO2'_8") (pintype "output"))
      (node (ref "J11") (pin "2") (pinfunction "1_2") (pintype "passive"))
    )
    (net (code "46") (name "Net-(HB3-AO1')") (class "Default")
      (node (ref "HB3") (pin "1") (pinfunction "AO1_1") (pintype "output"))
      (node (ref "HB3") (pin "2") (pinfunction "AO1'_2") (pintype "output"))
      (node (ref "J12") (pin "2") (pinfunction "1_2") (pintype "passive"))
    )
    (net (code "47") (name "Net-(HB3-AO2')") (class "Default")
      (node (ref "HB3") (pin "5") (pinfunction "AO2_5") (pintype "output"))
      (node (ref "HB3") (pin "6") (pinfunction "AO2'_6") (pintype "output"))
      (node (ref "J12") (pin "1") (pinfunction "2_1") (pintype "passive"))
    )
    (net (code "48") (name "Net-(HB3-BO1')") (class "Default")
      (node (ref "HB3") (pin "11") (pinfunction "BO1_11") (pintype "output"))
      (node (ref "HB3") (pin "12") (pinfunction "BO1'_12") (pintype "output"))
      (node (ref "J13") (pin "1") (pinfunction "2_1") (pintype "passive"))
    )
    (net (code "49") (name "Net-(HB3-BO2')") (class "Default")
      (node (ref "HB3") (pin "7") (pinfunction "BO2_7") (pintype "output"))
      (node (ref "HB3") (pin "8") (pinfunction "BO2'_8") (pintype "output"))
      (node (ref "J13") (pin "2") (pinfunction "1_2") (pintype "passive"))
    )
    (net (code "50") (name "Net-(HB4-AO1')") (class "Default")
      (node (ref "HB4") (pin "1") (pinfunction "AO1_1") (pintype "output"))
      (node (ref "HB4") (pin "2") (pinfunction "AO1'_2") (pintype "output"))
      (node (ref "J14") (pin "2") (pinfunction "1_2") (pintype "passive"))
    )
    (net (code "51") (name "Net-(HB4-AO2')") (class "Default")
      (node (ref "HB4") (pin "5") (pinfunction "AO2_5") (pintype "output"))
      (node (ref "HB4") (pin "6") (pinfunction "AO2'_6") (pintype "output"))
      (node (ref "J14") (pin "1") (pinfunction "2_1") (pintype "passive"))
    )
    (net (code "52") (name "Net-(HB4-BO1')") (class "Default")
      (node (ref "HB4") (pin "11") (pinfunction "BO1_11") (pintype "output"))
      (node (ref "HB4") (pin "12") (pinfunction "BO1'_12") (pintype "output"))
      (node (ref "J15") (pin "1") (pinfunction "2_1") (pintype "passive"))
    )
    (net (code "53") (name "Net-(HB4-BO2')") (class "Default")
      (node (ref "HB4") (pin "7") (pinfunction "BO2_7") (pintype "output"))
      (node (ref "HB4") (pin "8") (pinfunction "BO2'_8") (pintype "output"))
      (node (ref "J15") (pin "2") (pinfunction "1_2") (pintype "passive"))
    )
    (net (code "54") (name "Net-(Q1-B)") (class "Default")
      (node (ref "Q1") (pin "1") (pinfunction "B_1") (pintype "passive"))
      (node (ref "R10") (pin "2") (pinfunction "2_2") (pintype "passive"))
    )
    (net (code "55") (name "Net-(Q2-B)") (class "Default")
      (node (ref "Q2") (pin "1") (pinfunction "B_1") (pintype "passive"))
      (node (ref "R9") (pin "2") (pinfunction "2_2") (pintype "passive"))
    )
    (net (code "56") (name "Net-(Q3-S)") (class "Default")
      (node (ref "C6") (pin "1") (pinfunction "1_1") (pintype "passive"))
      (node (ref "D1") (pin "C") (pinfunction "C_C") (pintype "passive"))
      (node (ref "Q3") (pin "2") (pinfunction "S_2") (pintype "passive"))
      (node (ref "S1") (pin "3") (pinfunction "S_3") (pintype "passive"))
      (node (ref "U2") (pin "1") (pinfunction "IN_1") (pintype "power_in"))
    )
    (net (code "57") (name "Net-(S1-P)") (class "Default")
      (node (ref "S1") (pin "2") (pinfunction "P_2") (pintype "passive"))
      (node (ref "U2") (pin "3") (pinfunction "EN_3") (pintype "input"))
    )
    (net (code "58") (name "Net-(TP6-1)") (class "Default")
      (node (ref "TP6") (pin "P$1") (pinfunction "1_P$1") (pintype "bidirectional"))
      (node (ref "U9") (pin "13") (pinfunction "14-IO_13") (pintype "bidirectional"))
    )
    (net (code "59") (name "Net-(TP7-1)") (class "Default")
      (node (ref "TP7") (pin "P$1") (pinfunction "1_P$1") (pintype "bidirectional"))
      (node (ref "U9") (pin "7") (pinfunction "35-IA_7") (pintype "bidirectional"))
    )
    (net (code "60") (name "Net-(TP8-1)") (class "Default")
      (node (ref "TP8") (pin "P$1") (pinfunction "1_P$1") (pintype "bidirectional"))
      (node (ref "U9") (pin "6") (pinfunction "34-IA_6") (pintype "bidirectional"))
    )
    (net (code "61") (name "Net-(TP9-1)") (class "Default")
      (node (ref "TP9") (pin "P$1") (pinfunction "1_P$1") (pintype "bidirectional"))
      (node (ref "U9") (pin "5") (pinfunction "39-I_5") (pintype "bidirectional"))
    )
    (net (code "62") (name "Net-(TP10-1)") (class "Default")
      (node (ref "TP10") (pin "P$1") (pinfunction "1_P$1") (pintype "bidirectional"))
      (node (ref "U9") (pin "4") (pinfunction "36-I_4") (pintype "bidirectional"))
    )
    (net (code "63") (name "Net-(U1-2)") (class "Default")
      (node (ref "R7") (pin "1") (pinfunction "1_1") (pintype "passive"))
      (node (ref "U1") (pin "BLUE") (pinfunction "2_BLUE") (pintype "passive"))
    )
    (net (code "64") (name "Net-(U1-3)") (class "Default")
      (node (ref "R6") (pin "1") (pinfunction "1_1") (pintype "passive"))
      (node (ref "U1") (pin "GREEN") (pinfunction "3_GREEN") (pintype "passive"))
    )
    (net (code "65") (name "Net-(U1-4)") (class "Default")
      (node (ref "R5") (pin "1") (pinfunction "1_1") (pintype "passive"))
      (node (ref "U1") (pin "RED") (pinfunction "4_RED") (pintype "passive"))
    )
    (net (code "66") (name "Net-(U3-PROG)") (class "Default")
      (node (ref "JP1") (pin "1") (pinfunction "1_1") (pintype "passive"))
      (node (ref "R4") (pin "2") (pinfunction "2_2") (pintype "passive"))
      (node (ref "U3") (pin "5") (pinfunction "PROG_5") (pintype "input"))
    )
    (net (code "67") (name "Net-(U3-STAT)") (class "Default")
      (node (ref "R2") (pin "2") (pinfunction "2_2") (pintype "passive"))
      (node (ref "U3") (pin "1") (pinfunction "STAT_1") (pintype "output"))
    )
    (net (code "68") (name "Net-(U4-CAP)") (class "Default")
      (node (ref "C1") (pin "1") (pinfunction "1_1") (pintype "passive"))
      (node (ref "U4") (pin "9") (pinfunction "CAP_9") (pintype "bidirectional"))
    )
    (net (code "69") (name "Net-(U4-S_SCL)") (class "Default")
      (node (ref "R15") (pin "1") (pinfunction "1_1") (pintype "passive"))
      (node (ref "U4") (pin "15") (pinfunction "S_SCL_15") (pintype "bidirectional"))
    )
    (net (code "70") (name "Net-(U4-S_SDA)") (class "Default")
      (node (ref "R8") (pin "1") (pinfunction "1_1") (pintype "passive"))
      (node (ref "U4") (pin "16") (pinfunction "S_SDA_16") (pintype "bidirectional"))
    )
    (net (code "71") (name "Net-(U7A-D+)") (class "Default")
      (node (ref "J1") (pin "D+") (pinfunction "D+_D+") (pintype "bidirectional"))
      (node (ref "U7") (pin "3") (pinfunction "D+_3") (pintype "bidirectional"))
    )
    (net (code "72") (name "Net-(U7A-D-)") (class "Default")
      (node (ref "J1") (pin "D-") (pinfunction "D-_D-") (pintype "bidirectional"))
      (node (ref "U7") (pin "4") (pinfunction "D-_4") (pintype "bidirectional"))
    )
    (net (code "73") (name "RED") (class "Default")
      (node (ref "R5") (pin "2") (pinfunction "2_2") (pintype "passive"))
      (node (ref "TP20") (pin "P$1") (pinfunction "1_P$1") (pintype "bidirectional"))
      (node (ref "U9") (pin "31") (pinfunction "19-IO_31") (pintype "bidirectional"))
    )
    (net (code "74") (name "RTS") (class "Default")
      (node (ref "Q1") (pin "2") (pinfunction "E_2") (pintype "passive"))
      (node (ref "R9") (pin "1") (pinfunction "1_1") (pintype "passive"))
      (node (ref "U7") (pin "19") (pinfunction "RTS_19") (pintype "output"))
    )
    (net (code "75") (name "RX") (class "Default")
      (node (ref "U7") (pin "21") (pinfunction "TXD_21") (pintype "output"))
      (node (ref "U9") (pin "34") (pinfunction "RX_34") (pintype "bidirectional"))
    )
    (net (code "76") (name "S1-SIG") (class "Default")
      (node (ref "J4") (pin "3") (pinfunction "3_3") (pintype "passive"))
      (node (ref "TP2") (pin "P$1") (pinfunction "1_P$1") (pintype "bidirectional"))
      (node (ref "U9") (pin "9") (pinfunction "33-IOA_9") (pintype "bidirectional"))
    )
    (net (code "77") (name "S2-SIG") (class "Default")
      (node (ref "J5") (pin "3") (pinfunction "3_3") (pintype "passive"))
      (node (ref "TP1") (pin "P$1") (pinfunction "1_P$1") (pintype "bidirectional"))
      (node (ref "U9") (pin "8") (pinfunction "32-IOA_8") (pintype "bidirectional"))
    )
    (net (code "78") (name "S3-SIG") (class "Default")
      (node (ref "J6") (pin "3") (pinfunction "3_3") (pintype "passive"))
      (node (ref "TP14") (pin "P$1") (pinfunction "1_P$1") (pintype "bidirectional"))
      (node (ref "U9") (pin "37") (pinfunction "23-IO_37") (pintype "bidirectional"))
    )
    (net (code "79") (name "S4-SIG") (class "Default")
      (node (ref "J7") (pin "3") (pinfunction "3_3") (pintype "passive"))
      (node (ref "TP15") (pin "P$1") (pinfunction "1_P$1") (pintype "bidirectional"))
      (node (ref "U9") (pin "27") (pinfunction "16-IO_27") (pintype "bidirectional"))
    )
    (net (code "80") (name "SCL") (class "Default")
      (node (ref "R14") (pin "2") (pinfunction "2_2") (pintype "passive"))
      (node (ref "TP18") (pin "P$1") (pinfunction "1_P$1") (pintype "bidirectional"))
      (node (ref "U10") (pin "P$7") (pinfunction "SCL_P$7") (pintype "output"))
      (node (ref "U4") (pin "19") (pinfunction "H_SCL/SCLK/RX_19") (pintype "bidirectional"))
      (node (ref "U5") (pin "25") (pinfunction "SCL_25") (pintype "bidirectional"))
      (node (ref "U6") (pin "25") (pinfunction "SCL_25") (pintype "bidirectional"))
      (node (ref "U9") (pin "36") (pinfunction "22-IO_36") (pintype "bidirectional"))
    )
    (net (code "81") (name "SDA") (class "Default")
      (node (ref "R13") (pin "1") (pinfunction "1_1") (pintype "passive"))
      (node (ref "TP19") (pin "P$1") (pinfunction "1_P$1") (pintype "bidirectional"))
      (node (ref "U10") (pin "P$8") (pinfunction "SDA_P$8") (pintype "input"))
      (node (ref "U4") (pin "20") (pinfunction "H_SDA/MISO/TX_20") (pintype "bidirectional"))
      (node (ref "U5") (pin "24") (pinfunction "SDA_24") (pintype "bidirectional"))
      (node (ref "U6") (pin "24") (pinfunction "SDA_24") (pintype "bidirectional"))
      (node (ref "U9") (pin "33") (pinfunction "21-IO_33") (pintype "bidirectional"))
    )
    (net (code "82") (name "TX") (class "Default")
      (node (ref "U7") (pin "20") (pinfunction "RXD_20") (pintype "input"))
      (node (ref "U9") (pin "35") (pinfunction "TX_35") (pintype "bidirectional"))
    )
    (net (code "83") (name "VBAT") (class "Default")
      (node (ref "C11") (pin "1") (pinfunction "1_1") (pintype "passive"))
      (node (ref "C19") (pin "1") (pinfunction "1_1") (pintype "passive"))
      (node (ref "C22") (pin "1") (pinfunction "1_1") (pintype "passive"))
      (node (ref "C25") (pin "1") (pinfunction "1_1") (pintype "passive"))
      (node (ref "C28") (pin "+") (pinfunction "+_+") (pintype "passive"))
      (node (ref "C29") (pin "+") (pinfunction "+_+") (pintype "passive"))
      (node (ref "C3") (pin "1") (pinfunction "1_1") (pintype "passive"))
      (node (ref "C30") (pin "+") (pinfunction "+_+") (pintype "passive"))
      (node (ref "C31") (pin "+") (pinfunction "+_+") (pintype "passive"))
      (node (ref "C5") (pin "1") (pinfunction "1_1") (pintype "passive"))
      (node (ref "HB1") (pin "13") (pinfunction "VM2_13") (pintype "power_in"))
      (node (ref "HB1") (pin "14") (pinfunction "VM3_14") (pintype "power_in"))
      (node (ref "HB1") (pin "24") (pinfunction "VM1_24") (pintype "power_in"))
      (node (ref "HB2") (pin "13") (pinfunction "VM2_13") (pintype "power_in"))
      (node (ref "HB2") (pin "14") (pinfunction "VM3_14") (pintype "power_in"))
      (node (ref "HB2") (pin "24") (pinfunction "VM1_24") (pintype "power_in"))
      (node (ref "HB3") (pin "13") (pinfunction "VM2_13") (pintype "power_in"))
      (node (ref "HB3") (pin "14") (pinfunction "VM3_14") (pintype "power_in"))
      (node (ref "HB3") (pin "24") (pinfunction "VM1_24") (pintype "power_in"))
      (node (ref "HB4") (pin "13") (pinfunction "VM2_13") (pintype "power_in"))
      (node (ref "HB4") (pin "14") (pinfunction "VM3_14") (pintype "power_in"))
      (node (ref "HB4") (pin "24") (pinfunction "VM1_24") (pintype "power_in"))
      (node (ref "J2") (pin "2") (pinfunction "1_2") (pintype "passive"))
      (node (ref "J4") (pin "1") (pinfunction "1_1") (pintype "passive"))
      (node (ref "J5") (pin "1") (pinfunction "1_1") (pintype "passive"))
      (node (ref "J6") (pin "1") (pinfunction "1_1") (pintype "passive"))
      (node (ref "J7") (pin "1") (pinfunction "1_1") (pintype "passive"))
      (node (ref "Q3") (pin "3") (pinfunction "D_3") (pintype "passive"))
      (node (ref "U10") (pin "P$2") (pinfunction "CELL_P$2") (pintype "input"))
      (node (ref "U10") (pin "P$3") (pinfunction "VDD_P$3") (pintype "bidirectional"))
      (node (ref "U3") (pin "3") (pinfunction "VBAT_3") (pintype "power_in"))
    )
    (net (code "84") (name "VUSB") (class "Default")
      (node (ref "C9") (pin "1") (pinfunction "1_1") (pintype "passive"))
      (node (ref "D1") (pin "A") (pinfunction "A_A") (pintype "passive"))
      (node (ref "D2") (pin "A") (pinfunction "A_A") (pintype "passive"))
      (node (ref "J1") (pin "VBUS") (pinfunction "VBUS_VBUS") (pintype "power_in"))
      (node (ref "JP1") (pin "2") (pinfunction "2_2") (pintype "passive"))
      (node (ref "Q3") (pin "1") (pinfunction "G_1") (pintype "passive"))
      (node (ref "R12") (pin "2") (pinfunction "2_2") (pintype "passive"))
      (node (ref "U3") (pin "4") (pinfunction "VDD_4") (pintype "power_in"))
      (node (ref "U7") (pin "8") (pinfunction "VBUS_8") (pintype "power_in"))
    )
    (net (code "85") (name "unconnected-(J1-PadID)") (class "Default")
      (node (ref "J1") (pin "ID") (pinfunction "ID_ID") (pintype "bidirectional"))
    )
    (net (code "86") (name "unconnected-(U2-P4-Pad4)") (class "Default")
      (node (ref "U2") (pin "4") (pinfunction "P4_4") (pintype "bidirectional"))
    )
    (net (code "87") (name "unconnected-(U4-XIN32-Pad27)") (class "Default")
      (node (ref "U4") (pin "27") (pinfunction "XIN32_27") (pintype "bidirectional"))
    )
    (net (code "88") (name "unconnected-(U4-~{H_CS}-Pad18)") (class "Default")
      (node (ref "U4") (pin "18") (pinfunction "~{H_CS}_18") (pintype "bidirectional"))
    )
    (net (code "89") (name "unconnected-(U5-I{slash}O[0]-Pad27)") (class "Default")
      (node (ref "U5") (pin "27") (pinfunction "I/O[0]_27") (pintype "bidirectional"))
    )
    (net (code "90") (name "unconnected-(U5-I{slash}O[7]-Pad8)") (class "Default")
      (node (ref "U5") (pin "8") (pinfunction "I/O[7]_8") (pintype "bidirectional"))
    )
    (net (code "91") (name "unconnected-(U5-I{slash}O[8]-Pad13)") (class "Default")
      (node (ref "U5") (pin "13") (pinfunction "I/O[8]_13") (pintype "bidirectional"))
    )
    (net (code "92") (name "unconnected-(U5-I{slash}O[15]-Pad22)") (class "Default")
      (node (ref "U5") (pin "22") (pinfunction "I/O[15]_22") (pintype "bidirectional"))
    )
    (net (code "93") (name "unconnected-(U5-OSCIO-Pad11)") (class "Default")
      (node (ref "U5") (pin "11") (pinfunction "OSCIO_11") (pintype "bidirectional"))
    )
    (net (code "94") (name "unconnected-(U5-~{INT}-Pad9)") (class "Default")
      (node (ref "U5") (pin "9") (pinfunction "~{INT}_9") (pintype "bidirectional"))
    )
    (net (code "95") (name "unconnected-(U6-I{slash}O[0]-Pad27)") (class "Default")
      (node (ref "U6") (pin "27") (pinfunction "I/O[0]_27") (pintype "bidirectional"))
    )
    (net (code "96") (name "unconnected-(U6-I{slash}O[7]-Pad8)") (class "Default")
      (node (ref "U6") (pin "8") (pinfunction "I/O[7]_8") (pintype "bidirectional"))
    )
    (net (code "97") (name "unconnected-(U6-I{slash}O[8]-Pad13)") (class "Default")
      (node (ref "U6") (pin "13") (pinfunction "I/O[8]_13") (pintype "bidirectional"))
    )
    (net (code "98") (name "unconnected-(U6-I{slash}O[15]-Pad22)") (class "Default")
      (node (ref "U6") (pin "22") (pinfunction "I/O[15]_22") (pintype "bidirectional"))
    )
    (net (code "99") (name "unconnected-(U6-OSCIO-Pad11)") (class "Default")
      (node (ref "U6") (pin "11") (pinfunction "OSCIO_11") (pintype "bidirectional"))
    )
    (net (code "100") (name "unconnected-(U6-~{INT}-Pad9)") (class "Default")
      (node (ref "U6") (pin "9") (pinfunction "~{INT}_9") (pintype "bidirectional"))
    )
    (net (code "101") (name "unconnected-(U7A-#RST-Pad9)") (class "Default")
      (node (ref "U7") (pin "9") (pinfunction "#RST_9") (pintype "bidirectional"))
    )
    (net (code "102") (name "unconnected-(U7A-#SUSPEND-Pad15)") (class "Default")
      (node (ref "U7") (pin "15") (pinfunction "#SUSPEND_15") (pintype "output"))
    )
    (net (code "103") (name "unconnected-(U7A-CTS-Pad18)") (class "Default")
      (node (ref "U7") (pin "18") (pinfunction "CTS_18") (pintype "input"))
    )
    (net (code "104") (name "unconnected-(U7A-DCD-Pad24)") (class "Default")
      (node (ref "U7") (pin "24") (pinfunction "DCD_24") (pintype "input"))
    )
    (net (code "105") (name "unconnected-(U7A-DSR-Pad22)") (class "Default")
      (node (ref "U7") (pin "22") (pinfunction "DSR_22") (pintype "input"))
    )
    (net (code "106") (name "unconnected-(U7A-GPIO0{slash}TXLED-Pad14)") (class "Default")
      (node (ref "U7") (pin "14") (pinfunction "GPIO0/TXLED_14") (pintype "bidirectional"))
    )
    (net (code "107") (name "unconnected-(U7A-GPIO1{slash}RXLED-Pad13)") (class "Default")
      (node (ref "U7") (pin "13") (pinfunction "GPIO1/RXLED_13") (pintype "bidirectional"))
    )
    (net (code "108") (name "unconnected-(U7A-GPIO2-Pad12)") (class "Default")
      (node (ref "U7") (pin "12") (pinfunction "GPIO2_12") (pintype "bidirectional"))
    )
    (net (code "109") (name "unconnected-(U7A-GPIO3-Pad11)") (class "Default")
      (node (ref "U7") (pin "11") (pinfunction "GPIO3_11") (pintype "bidirectional"))
    )
    (net (code "110") (name "unconnected-(U7A-NC-Pad10)") (class "Default")
      (node (ref "U7") (pin "10") (pinfunction "NC_10") (pintype "no_connect"))
    )
    (net (code "111") (name "unconnected-(U7A-RI-Pad1)") (class "Default")
      (node (ref "U7") (pin "1") (pinfunction "RI_1") (pintype "input"))
    )
    (net (code "112") (name "unconnected-(U7A-SUSPEND-Pad17)") (class "Default")
      (node (ref "U7") (pin "17") (pinfunction "SUSPEND_17") (pintype "output"))
    )
    (net (code "113") (name "unconnected-(U7A-VPP-Pad16)") (class "Default")
      (node (ref "U7") (pin "16") (pinfunction "VPP_16") (pintype "bidirectional"))
    )
    (net (code "114") (name "unconnected-(U9-2-Pad24)") (class "Default")
      (node (ref "U9") (pin "24") (pinfunction "2_24") (pintype "bidirectional"))
    )
    (net (code "115") (name "unconnected-(U9-5-Pad29)") (class "Default")
      (node (ref "U9") (pin "29") (pinfunction "5_29") (pintype "bidirectional"))
    )
    (net (code "116") (name "unconnected-(U9-12-Pad14)") (class "Default")
      (node (ref "U9") (pin "14") (pinfunction "12_14") (pintype "bidirectional"))
    )
    (net (code "117") (name "unconnected-(U9-15-Pad23)") (class "Default")
      (node (ref "U9") (pin "23") (pinfunction "15_23") (pintype "bidirectional"))
    )
    (net (code "118") (name "unconnected-(U9-NC-Pad32)") (class "Default")
      (node (ref "U9") (pin "32") (pinfunction "NC_32") (pintype "bidirectional"))
    )
    (net (code "119") (name "unconnected-(U9-SCK-Pad20)") (class "Default")
      (node (ref "U9") (pin "20") (pinfunction "SCK_20") (pintype "bidirectional"))
    )
    (net (code "120") (name "unconnected-(U9-SCS-Pad19)") (class "Default")
      (node (ref "U9") (pin "19") (pinfunction "SCS_19") (pintype "bidirectional"))
    )
    (net (code "121") (name "unconnected-(U9-SDI-Pad22)") (class "Default")
      (node (ref "U9") (pin "22") (pinfunction "SDI_22") (pintype "bidirectional"))
    )
    (net (code "122") (name "unconnected-(U9-SDO-Pad21)") (class "Default")
      (node (ref "U9") (pin "21") (pinfunction "SDO_21") (pintype "bidirectional"))
    )
    (net (code "123") (name "unconnected-(U9-SHD-Pad17)") (class "Default")
      (node (ref "U9") (pin "17") (pinfunction "SHD_17") (pintype "bidirectional"))
    )
    (net (code "124") (name "unconnected-(U9-SWP-Pad18)") (class "Default")
      (node (ref "U9") (pin "18") (pinfunction "SWP_18") (pintype "bidirectional"))
    )
    (net (code "125") (name "unconnected-(U10-~{ALRT}-PadP$5)") (class "Default")
      (node (ref "U10") (pin "P$5") (pinfunction "~{ALRT}_P$5") (pintype "bidirectional"))
    )
  )
)
